# TaaraWeMosBase3.net
KiCad netlist of a schematic drawn in EAGLE
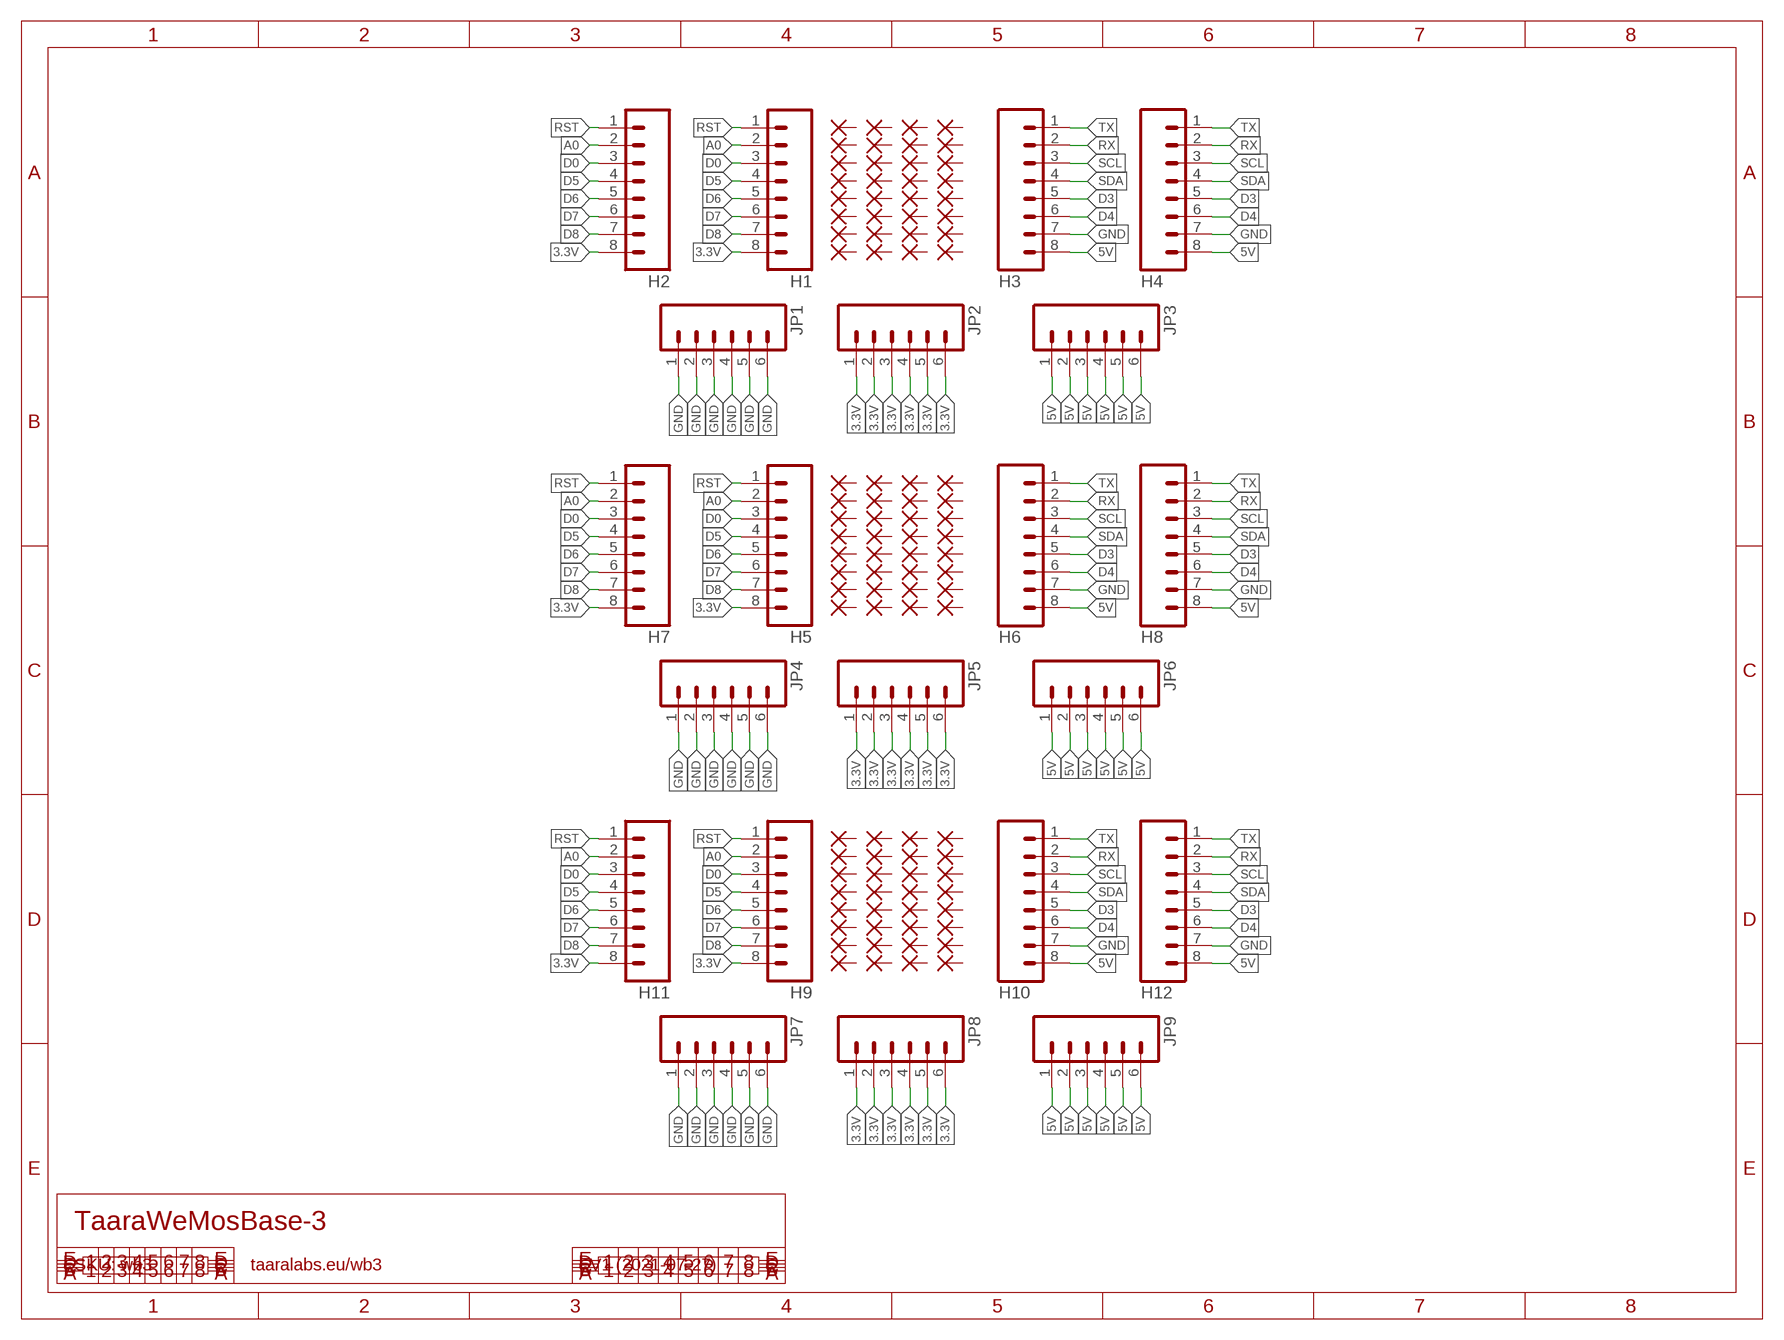
[diagram p0: schematic, sheet 1]

(export (version "E")
  (design (tool "Eeschema 10.0.6"))
  (components
    (comp (ref "H1")
      (value "M08")
      (footprint "eagle-import:1X08")
      (libsource (lib "eagle-import") (part "M08"))
    )
    (comp (ref "H2")
      (value "M08")
      (footprint "eagle-import:1X08")
      (libsource (lib "eagle-import") (part "M08"))
    )
    (comp (ref "H3")
      (value "M08")
      (footprint "eagle-import:1X08")
      (libsource (lib "eagle-import") (part "M08"))
    )
    (comp (ref "H4")
      (value "M08")
      (footprint "eagle-import:1X08")
      (libsource (lib "eagle-import") (part "M08"))
    )
    (comp (ref "H5")
      (value "M08")
      (footprint "eagle-import:1X08")
      (libsource (lib "eagle-import") (part "M08"))
    )
    (comp (ref "H6")
      (value "M08")
      (footprint "eagle-import:1X08")
      (libsource (lib "eagle-import") (part "M08"))
    )
    (comp (ref "H7")
      (value "M08")
      (footprint "eagle-import:1X08")
      (libsource (lib "eagle-import") (part "M08"))
    )
    (comp (ref "H8")
      (value "M08")
      (footprint "eagle-import:1X08")
      (libsource (lib "eagle-import") (part "M08"))
    )
    (comp (ref "H9")
      (value "M08")
      (footprint "eagle-import:1X08")
      (libsource (lib "eagle-import") (part "M08"))
    )
    (comp (ref "H10")
      (value "M08")
      (footprint "eagle-import:1X08")
      (libsource (lib "eagle-import") (part "M08"))
    )
    (comp (ref "H11")
      (value "M08")
      (footprint "eagle-import:1X08")
      (libsource (lib "eagle-import") (part "M08"))
    )
    (comp (ref "H12")
      (value "M08")
      (footprint "eagle-import:1X08")
      (libsource (lib "eagle-import") (part "M08"))
    )
    (comp (ref "JP1")
      (value "M06SIP")
      (footprint "eagle-import:1X06")
      (libsource (lib "eagle-import") (part "M06SIP"))
    )
    (comp (ref "JP2")
      (value "M06SIP")
      (footprint "eagle-import:1X06")
      (libsource (lib "eagle-import") (part "M06SIP"))
    )
    (comp (ref "JP3")
      (value "M06SIP")
      (footprint "eagle-import:1X06")
      (libsource (lib "eagle-import") (part "M06SIP"))
    )
    (comp (ref "JP4")
      (value "M06SIP")
      (footprint "eagle-import:1X06")
      (libsource (lib "eagle-import") (part "M06SIP"))
    )
    (comp (ref "JP5")
      (value "M06SIP")
      (footprint "eagle-import:1X06")
      (libsource (lib "eagle-import") (part "M06SIP"))
    )
    (comp (ref "JP6")
      (value "M06SIP")
      (footprint "eagle-import:1X06")
      (libsource (lib "eagle-import") (part "M06SIP"))
    )
    (comp (ref "JP7")
      (value "M06SIP")
      (footprint "eagle-import:1X06")
      (libsource (lib "eagle-import") (part "M06SIP"))
    )
    (comp (ref "JP8")
      (value "M06SIP")
      (footprint "eagle-import:1X06")
      (libsource (lib "eagle-import") (part "M06SIP"))
    )
    (comp (ref "JP9")
      (value "M06SIP")
      (footprint "eagle-import:1X06")
      (libsource (lib "eagle-import") (part "M06SIP"))
    )
    (comp (ref "PAD1")
      (value "1,6/0,8")
      (footprint "eagle-import:1,6_0,8")
      (libsource (lib "eagle-import") (part "1,6/0,8"))
    )
    (comp (ref "PAD2")
      (value "1,6/0,8")
      (footprint "eagle-import:1,6_0,8")
      (libsource (lib "eagle-import") (part "1,6/0,8"))
    )
    (comp (ref "PAD3")
      (value "1,6/0,8")
      (footprint "eagle-import:1,6_0,8")
      (libsource (lib "eagle-import") (part "1,6/0,8"))
    )
    (comp (ref "PAD4")
      (value "1,6/0,8")
      (footprint "eagle-import:1,6_0,8")
      (libsource (lib "eagle-import") (part "1,6/0,8"))
    )
    (comp (ref "PAD5")
      (value "1,6/0,8")
      (footprint "eagle-import:1,6_0,8")
      (libsource (lib "eagle-import") (part "1,6/0,8"))
    )
    (comp (ref "PAD6")
      (value "1,6/0,8")
      (footprint "eagle-import:1,6_0,8")
      (libsource (lib "eagle-import") (part "1,6/0,8"))
    )
    (comp (ref "PAD7")
      (value "1,6/0,8")
      (footprint "eagle-import:1,6_0,8")
      (libsource (lib "eagle-import") (part "1,6/0,8"))
    )
    (comp (ref "PAD8")
      (value "1,6/0,8")
      (footprint "eagle-import:1,6_0,8")
      (libsource (lib "eagle-import") (part "1,6/0,8"))
    )
    (comp (ref "PAD9")
      (value "1,6/0,8")
      (footprint "eagle-import:1,6_0,8")
      (libsource (lib "eagle-import") (part "1,6/0,8"))
    )
    (comp (ref "PAD10")
      (value "1,6/0,8")
      (footprint "eagle-import:1,6_0,8")
      (libsource (lib "eagle-import") (part "1,6/0,8"))
    )
    (comp (ref "PAD11")
      (value "1,6/0,8")
      (footprint "eagle-import:1,6_0,8")
      (libsource (lib "eagle-import") (part "1,6/0,8"))
    )
    (comp (ref "PAD12")
      (value "1,6/0,8")
      (footprint "eagle-import:1,6_0,8")
      (libsource (lib "eagle-import") (part "1,6/0,8"))
    )
    (comp (ref "PAD13")
      (value "1,6/0,8")
      (footprint "eagle-import:1,6_0,8")
      (libsource (lib "eagle-import") (part "1,6/0,8"))
    )
    (comp (ref "PAD14")
      (value "1,6/0,8")
      (footprint "eagle-import:1,6_0,8")
      (libsource (lib "eagle-import") (part "1,6/0,8"))
    )
    (comp (ref "PAD15")
      (value "1,6/0,8")
      (footprint "eagle-import:1,6_0,8")
      (libsource (lib "eagle-import") (part "1,6/0,8"))
    )
    (comp (ref "PAD16")
      (value "1,6/0,8")
      (footprint "eagle-import:1,6_0,8")
      (libsource (lib "eagle-import") (part "1,6/0,8"))
    )
    (comp (ref "PAD17")
      (value "1,6/0,8")
      (footprint "eagle-import:1,6_0,8")
      (libsource (lib "eagle-import") (part "1,6/0,8"))
    )
    (comp (ref "PAD18")
      (value "1,6/0,8")
      (footprint "eagle-import:1,6_0,8")
      (libsource (lib "eagle-import") (part "1,6/0,8"))
    )
    (comp (ref "PAD19")
      (value "1,6/0,8")
      (footprint "eagle-import:1,6_0,8")
      (libsource (lib "eagle-import") (part "1,6/0,8"))
    )
    (comp (ref "PAD20")
      (value "1,6/0,8")
      (footprint "eagle-import:1,6_0,8")
      (libsource (lib "eagle-import") (part "1,6/0,8"))
    )
    (comp (ref "PAD21")
      (value "1,6/0,8")
      (footprint "eagle-import:1,6_0,8")
      (libsource (lib "eagle-import") (part "1,6/0,8"))
    )
    (comp (ref "PAD22")
      (value "1,6/0,8")
      (footprint "eagle-import:1,6_0,8")
      (libsource (lib "eagle-import") (part "1,6/0,8"))
    )
    (comp (ref "PAD23")
      (value "1,6/0,8")
      (footprint "eagle-import:1,6_0,8")
      (libsource (lib "eagle-import") (part "1,6/0,8"))
    )
    (comp (ref "PAD24")
      (value "1,6/0,8")
      (footprint "eagle-import:1,6_0,8")
      (libsource (lib "eagle-import") (part "1,6/0,8"))
    )
    (comp (ref "PAD25")
      (value "1,6/0,8")
      (footprint "eagle-import:1,6_0,8")
      (libsource (lib "eagle-import") (part "1,6/0,8"))
    )
    (comp (ref "PAD26")
      (value "1,6/0,8")
      (footprint "eagle-import:1,6_0,8")
      (libsource (lib "eagle-import") (part "1,6/0,8"))
    )
    (comp (ref "PAD27")
      (value "1,6/0,8")
      (footprint "eagle-import:1,6_0,8")
      (libsource (lib "eagle-import") (part "1,6/0,8"))
    )
    (comp (ref "PAD28")
      (value "1,6/0,8")
      (footprint "eagle-import:1,6_0,8")
      (libsource (lib "eagle-import") (part "1,6/0,8"))
    )
    (comp (ref "PAD29")
      (value "1,6/0,8")
      (footprint "eagle-import:1,6_0,8")
      (libsource (lib "eagle-import") (part "1,6/0,8"))
    )
    (comp (ref "PAD30")
      (value "1,6/0,8")
      (footprint "eagle-import:1,6_0,8")
      (libsource (lib "eagle-import") (part "1,6/0,8"))
    )
    (comp (ref "PAD31")
      (value "1,6/0,8")
      (footprint "eagle-import:1,6_0,8")
      (libsource (lib "eagle-import") (part "1,6/0,8"))
    )
    (comp (ref "PAD32")
      (value "1,6/0,8")
      (footprint "eagle-import:1,6_0,8")
      (libsource (lib "eagle-import") (part "1,6/0,8"))
    )
    (comp (ref "PAD33")
      (value "1,6/0,8")
      (footprint "eagle-import:1,6_0,8")
      (libsource (lib "eagle-import") (part "1,6/0,8"))
    )
    (comp (ref "PAD34")
      (value "1,6/0,8")
      (footprint "eagle-import:1,6_0,8")
      (libsource (lib "eagle-import") (part "1,6/0,8"))
    )
    (comp (ref "PAD35")
      (value "1,6/0,8")
      (footprint "eagle-import:1,6_0,8")
      (libsource (lib "eagle-import") (part "1,6/0,8"))
    )
    (comp (ref "PAD36")
      (value "1,6/0,8")
      (footprint "eagle-import:1,6_0,8")
      (libsource (lib "eagle-import") (part "1,6/0,8"))
    )
    (comp (ref "PAD37")
      (value "1,6/0,8")
      (footprint "eagle-import:1,6_0,8")
      (libsource (lib "eagle-import") (part "1,6/0,8"))
    )
    (comp (ref "PAD38")
      (value "1,6/0,8")
      (footprint "eagle-import:1,6_0,8")
      (libsource (lib "eagle-import") (part "1,6/0,8"))
    )
    (comp (ref "PAD39")
      (value "1,6/0,8")
      (footprint "eagle-import:1,6_0,8")
      (libsource (lib "eagle-import") (part "1,6/0,8"))
    )
    (comp (ref "PAD40")
      (value "1,6/0,8")
      (footprint "eagle-import:1,6_0,8")
      (libsource (lib "eagle-import") (part "1,6/0,8"))
    )
    (comp (ref "PAD41")
      (value "1,6/0,8")
      (footprint "eagle-import:1,6_0,8")
      (libsource (lib "eagle-import") (part "1,6/0,8"))
    )
    (comp (ref "PAD42")
      (value "1,6/0,8")
      (footprint "eagle-import:1,6_0,8")
      (libsource (lib "eagle-import") (part "1,6/0,8"))
    )
    (comp (ref "PAD43")
      (value "1,6/0,8")
      (footprint "eagle-import:1,6_0,8")
      (libsource (lib "eagle-import") (part "1,6/0,8"))
    )
    (comp (ref "PAD44")
      (value "1,6/0,8")
      (footprint "eagle-import:1,6_0,8")
      (libsource (lib "eagle-import") (part "1,6/0,8"))
    )
    (comp (ref "PAD45")
      (value "1,6/0,8")
      (footprint "eagle-import:1,6_0,8")
      (libsource (lib "eagle-import") (part "1,6/0,8"))
    )
    (comp (ref "PAD46")
      (value "1,6/0,8")
      (footprint "eagle-import:1,6_0,8")
      (libsource (lib "eagle-import") (part "1,6/0,8"))
    )
    (comp (ref "PAD47")
      (value "1,6/0,8")
      (footprint "eagle-import:1,6_0,8")
      (libsource (lib "eagle-import") (part "1,6/0,8"))
    )
    (comp (ref "PAD48")
      (value "1,6/0,8")
      (footprint "eagle-import:1,6_0,8")
      (libsource (lib "eagle-import") (part "1,6/0,8"))
    )
    (comp (ref "PAD49")
      (value "1,6/0,8")
      (footprint "eagle-import:1,6_0,8")
      (libsource (lib "eagle-import") (part "1,6/0,8"))
    )
    (comp (ref "PAD50")
      (value "1,6/0,8")
      (footprint "eagle-import:1,6_0,8")
      (libsource (lib "eagle-import") (part "1,6/0,8"))
    )
    (comp (ref "PAD51")
      (value "1,6/0,8")
      (footprint "eagle-import:1,6_0,8")
      (libsource (lib "eagle-import") (part "1,6/0,8"))
    )
    (comp (ref "PAD52")
      (value "1,6/0,8")
      (footprint "eagle-import:1,6_0,8")
      (libsource (lib "eagle-import") (part "1,6/0,8"))
    )
    (comp (ref "PAD53")
      (value "1,6/0,8")
      (footprint "eagle-import:1,6_0,8")
      (libsource (lib "eagle-import") (part "1,6/0,8"))
    )
    (comp (ref "PAD54")
      (value "1,6/0,8")
      (footprint "eagle-import:1,6_0,8")
      (libsource (lib "eagle-import") (part "1,6/0,8"))
    )
    (comp (ref "PAD55")
      (value "1,6/0,8")
      (footprint "eagle-import:1,6_0,8")
      (libsource (lib "eagle-import") (part "1,6/0,8"))
    )
    (comp (ref "PAD56")
      (value "1,6/0,8")
      (footprint "eagle-import:1,6_0,8")
      (libsource (lib "eagle-import") (part "1,6/0,8"))
    )
    (comp (ref "PAD57")
      (value "1,6/0,8")
      (footprint "eagle-import:1,6_0,8")
      (libsource (lib "eagle-import") (part "1,6/0,8"))
    )
    (comp (ref "PAD58")
      (value "1,6/0,8")
      (footprint "eagle-import:1,6_0,8")
      (libsource (lib "eagle-import") (part "1,6/0,8"))
    )
    (comp (ref "PAD59")
      (value "1,6/0,8")
      (footprint "eagle-import:1,6_0,8")
      (libsource (lib "eagle-import") (part "1,6/0,8"))
    )
    (comp (ref "PAD60")
      (value "1,6/0,8")
      (footprint "eagle-import:1,6_0,8")
      (libsource (lib "eagle-import") (part "1,6/0,8"))
    )
    (comp (ref "PAD61")
      (value "1,6/0,8")
      (footprint "eagle-import:1,6_0,8")
      (libsource (lib "eagle-import") (part "1,6/0,8"))
    )
    (comp (ref "PAD62")
      (value "1,6/0,8")
      (footprint "eagle-import:1,6_0,8")
      (libsource (lib "eagle-import") (part "1,6/0,8"))
    )
    (comp (ref "PAD63")
      (value "1,6/0,8")
      (footprint "eagle-import:1,6_0,8")
      (libsource (lib "eagle-import") (part "1,6/0,8"))
    )
    (comp (ref "PAD64")
      (value "1,6/0,8")
      (footprint "eagle-import:1,6_0,8")
      (libsource (lib "eagle-import") (part "1,6/0,8"))
    )
    (comp (ref "PAD65")
      (value "1,6/0,8")
      (footprint "eagle-import:1,6_0,8")
      (libsource (lib "eagle-import") (part "1,6/0,8"))
    )
    (comp (ref "PAD66")
      (value "1,6/0,8")
      (footprint "eagle-import:1,6_0,8")
      (libsource (lib "eagle-import") (part "1,6/0,8"))
    )
    (comp (ref "PAD67")
      (value "1,6/0,8")
      (footprint "eagle-import:1,6_0,8")
      (libsource (lib "eagle-import") (part "1,6/0,8"))
    )
    (comp (ref "PAD68")
      (value "1,6/0,8")
      (footprint "eagle-import:1,6_0,8")
      (libsource (lib "eagle-import") (part "1,6/0,8"))
    )
    (comp (ref "PAD69")
      (value "1,6/0,8")
      (footprint "eagle-import:1,6_0,8")
      (libsource (lib "eagle-import") (part "1,6/0,8"))
    )
    (comp (ref "PAD70")
      (value "1,6/0,8")
      (footprint "eagle-import:1,6_0,8")
      (libsource (lib "eagle-import") (part "1,6/0,8"))
    )
    (comp (ref "PAD71")
      (value "1,6/0,8")
      (footprint "eagle-import:1,6_0,8")
      (libsource (lib "eagle-import") (part "1,6/0,8"))
    )
    (comp (ref "PAD72")
      (value "1,6/0,8")
      (footprint "eagle-import:1,6_0,8")
      (libsource (lib "eagle-import") (part "1,6/0,8"))
    )
    (comp (ref "PAD73")
      (value "1,6/0,8")
      (footprint "eagle-import:1,6_0,8")
      (libsource (lib "eagle-import") (part "1,6/0,8"))
    )
    (comp (ref "PAD74")
      (value "1,6/0,8")
      (footprint "eagle-import:1,6_0,8")
      (libsource (lib "eagle-import") (part "1,6/0,8"))
    )
    (comp (ref "PAD75")
      (value "1,6/0,8")
      (footprint "eagle-import:1,6_0,8")
      (libsource (lib "eagle-import") (part "1,6/0,8"))
    )
    (comp (ref "PAD76")
      (value "1,6/0,8")
      (footprint "eagle-import:1,6_0,8")
      (libsource (lib "eagle-import") (part "1,6/0,8"))
    )
    (comp (ref "PAD77")
      (value "1,6/0,8")
      (footprint "eagle-import:1,6_0,8")
      (libsource (lib "eagle-import") (part "1,6/0,8"))
    )
    (comp (ref "PAD78")
      (value "1,6/0,8")
      (footprint "eagle-import:1,6_0,8")
      (libsource (lib "eagle-import") (part "1,6/0,8"))
    )
    (comp (ref "PAD79")
      (value "1,6/0,8")
      (footprint "eagle-import:1,6_0,8")
      (libsource (lib "eagle-import") (part "1,6/0,8"))
    )
    (comp (ref "PAD80")
      (value "1,6/0,8")
      (footprint "eagle-import:1,6_0,8")
      (libsource (lib "eagle-import") (part "1,6/0,8"))
    )
    (comp (ref "PAD81")
      (value "1,6/0,8")
      (footprint "eagle-import:1,6_0,8")
      (libsource (lib "eagle-import") (part "1,6/0,8"))
    )
    (comp (ref "PAD82")
      (value "1,6/0,8")
      (footprint "eagle-import:1,6_0,8")
      (libsource (lib "eagle-import") (part "1,6/0,8"))
    )
    (comp (ref "PAD83")
      (value "1,6/0,8")
      (footprint "eagle-import:1,6_0,8")
      (libsource (lib "eagle-import") (part "1,6/0,8"))
    )
    (comp (ref "PAD84")
      (value "1,6/0,8")
      (footprint "eagle-import:1,6_0,8")
      (libsource (lib "eagle-import") (part "1,6/0,8"))
    )
    (comp (ref "PAD85")
      (value "1,6/0,8")
      (footprint "eagle-import:1,6_0,8")
      (libsource (lib "eagle-import") (part "1,6/0,8"))
    )
    (comp (ref "PAD86")
      (value "1,6/0,8")
      (footprint "eagle-import:1,6_0,8")
      (libsource (lib "eagle-import") (part "1,6/0,8"))
    )
    (comp (ref "PAD87")
      (value "1,6/0,8")
      (footprint "eagle-import:1,6_0,8")
      (libsource (lib "eagle-import") (part "1,6/0,8"))
    )
    (comp (ref "PAD88")
      (value "1,6/0,8")
      (footprint "eagle-import:1,6_0,8")
      (libsource (lib "eagle-import") (part "1,6/0,8"))
    )
    (comp (ref "PAD89")
      (value "1,6/0,8")
      (footprint "eagle-import:1,6_0,8")
      (libsource (lib "eagle-import") (part "1,6/0,8"))
    )
    (comp (ref "PAD90")
      (value "1,6/0,8")
      (footprint "eagle-import:1,6_0,8")
      (libsource (lib "eagle-import") (part "1,6/0,8"))
    )
    (comp (ref "PAD91")
      (value "1,6/0,8")
      (footprint "eagle-import:1,6_0,8")
      (libsource (lib "eagle-import") (part "1,6/0,8"))
    )
    (comp (ref "PAD92")
      (value "1,6/0,8")
      (footprint "eagle-import:1,6_0,8")
      (libsource (lib "eagle-import") (part "1,6/0,8"))
    )
    (comp (ref "PAD93")
      (value "1,6/0,8")
      (footprint "eagle-import:1,6_0,8")
      (libsource (lib "eagle-import") (part "1,6/0,8"))
    )
    (comp (ref "PAD94")
      (value "1,6/0,8")
      (footprint "eagle-import:1,6_0,8")
      (libsource (lib "eagle-import") (part "1,6/0,8"))
    )
    (comp (ref "PAD95")
      (value "1,6/0,8")
      (footprint "eagle-import:1,6_0,8")
      (libsource (lib "eagle-import") (part "1,6/0,8"))
    )
    (comp (ref "PAD96")
      (value "1,6/0,8")
      (footprint "eagle-import:1,6_0,8")
      (libsource (lib "eagle-import") (part "1,6/0,8"))
    )
  )
  (nets
    (net (code "1") (name "3.3V") (class "Default")
      (node (ref "H1") (pin "8") (pinfunction "8_8") (pintype "passive"))
      (node (ref "H11") (pin "8") (pinfunction "8_8") (pintype "passive"))
      (node (ref "H2") (pin "8") (pinfunction "8_8") (pintype "passive"))
      (node (ref "H5") (pin "8") (pinfunction "8_8") (pintype "passive"))
      (node (ref "H7") (pin "8") (pinfunction "8_8") (pintype "passive"))
      (node (ref "H9") (pin "8") (pinfunction "8_8") (pintype "passive"))
      (node (ref "JP2") (pin "1") (pinfunction "1_1") (pintype "passive"))
      (node (ref "JP2") (pin "2") (pinfunction "2_2") (pintype "passive"))
      (node (ref "JP2") (pin "3") (pinfunction "3_3") (pintype "passive"))
      (node (ref "JP2") (pin "4") (pinfunction "4_4") (pintype "passive"))
      (node (ref "JP2") (pin "5") (pinfunction "5_5") (pintype "passive"))
      (node (ref "JP2") (pin "6") (pinfunction "6_6") (pintype "passive"))
      (node (ref "JP5") (pin "1") (pinfunction "1_1") (pintype "passive"))
      (node (ref "JP5") (pin "2") (pinfunction "2_2") (pintype "passive"))
      (node (ref "JP5") (pin "3") (pinfunction "3_3") (pintype "passive"))
      (node (ref "JP5") (pin "4") (pinfunction "4_4") (pintype "passive"))
      (node (ref "JP5") (pin "5") (pinfunction "5_5") (pintype "passive"))
      (node (ref "JP5") (pin "6") (pinfunction "6_6") (pintype "passive"))
      (node (ref "JP8") (pin "1") (pinfunction "1_1") (pintype "passive"))
      (node (ref "JP8") (pin "2") (pinfunction "2_2") (pintype "passive"))
      (node (ref "JP8") (pin "3") (pinfunction "3_3") (pintype "passive"))
      (node (ref "JP8") (pin "4") (pinfunction "4_4") (pintype "passive"))
      (node (ref "JP8") (pin "5") (pinfunction "5_5") (pintype "passive"))
      (node (ref "JP8") (pin "6") (pinfunction "6_6") (pintype "passive"))
    )
    (net (code "2") (name "5V") (class "Default")
      (node (ref "H10") (pin "8") (pinfunction "8_8") (pintype "passive"))
      (node (ref "H12") (pin "8") (pinfunction "8_8") (pintype "passive"))
      (node (ref "H3") (pin "8") (pinfunction "8_8") (pintype "passive"))
      (node (ref "H4") (pin "8") (pinfunction "8_8") (pintype "passive"))
      (node (ref "H6") (pin "8") (pinfunction "8_8") (pintype "passive"))
      (node (ref "H8") (pin "8") (pinfunction "8_8") (pintype "passive"))
      (node (ref "JP3") (pin "1") (pinfunction "1_1") (pintype "passive"))
      (node (ref "JP3") (pin "2") (pinfunction "2_2") (pintype "passive"))
      (node (ref "JP3") (pin "3") (pinfunction "3_3") (pintype "passive"))
      (node (ref "JP3") (pin "4") (pinfunction "4_4") (pintype "passive"))
      (node (ref "JP3") (pin "5") (pinfunction "5_5") (pintype "passive"))
      (node (ref "JP3") (pin "6") (pinfunction "6_6") (pintype "passive"))
      (node (ref "JP6") (pin "1") (pinfunction "1_1") (pintype "passive"))
      (node (ref "JP6") (pin "2") (pinfunction "2_2") (pintype "passive"))
      (node (ref "JP6") (pin "3") (pinfunction "3_3") (pintype "passive"))
      (node (ref "JP6") (pin "4") (pinfunction "4_4") (pintype "passive"))
      (node (ref "JP6") (pin "5") (pinfunction "5_5") (pintype "passive"))
      (node (ref "JP6") (pin "6") (pinfunction "6_6") (pintype "passive"))
      (node (ref "JP9") (pin "1") (pinfunction "1_1") (pintype "passive"))
      (node (ref "JP9") (pin "2") (pinfunction "2_2") (pintype "passive"))
      (node (ref "JP9") (pin "3") (pinfunction "3_3") (pintype "passive"))
      (node (ref "JP9") (pin "4") (pinfunction "4_4") (pintype "passive"))
      (node (ref "JP9") (pin "5") (pinfunction "5_5") (pintype "passive"))
      (node (ref "JP9") (pin "6") (pinfunction "6_6") (pintype "passive"))
    )
    (net (code "3") (name "A0") (class "Default")
      (node (ref "H1") (pin "2") (pinfunction "2_2") (pintype "passive"))
      (node (ref "H11") (pin "2") (pinfunction "2_2") (pintype "passive"))
      (node (ref "H2") (pin "2") (pinfunction "2_2") (pintype "passive"))
      (node (ref "H5") (pin "2") (pinfunction "2_2") (pintype "passive"))
      (node (ref "H7") (pin "2") (pinfunction "2_2") (pintype "passive"))
      (node (ref "H9") (pin "2") (pinfunction "2_2") (pintype "passive"))
    )
    (net (code "4") (name "D0") (class "Default")
      (node (ref "H1") (pin "3") (pinfunction "3_3") (pintype "passive"))
      (node (ref "H11") (pin "3") (pinfunction "3_3") (pintype "passive"))
      (node (ref "H2") (pin "3") (pinfunction "3_3") (pintype "passive"))
      (node (ref "H5") (pin "3") (pinfunction "3_3") (pintype "passive"))
      (node (ref "H7") (pin "3") (pinfunction "3_3") (pintype "passive"))
      (node (ref "H9") (pin "3") (pinfunction "3_3") (pintype "passive"))
    )
    (net (code "5") (name "D3") (class "Default")
      (node (ref "H10") (pin "5") (pinfunction "5_5") (pintype "passive"))
      (node (ref "H12") (pin "5") (pinfunction "5_5") (pintype "passive"))
      (node (ref "H3") (pin "5") (pinfunction "5_5") (pintype "passive"))
      (node (ref "H4") (pin "5") (pinfunction "5_5") (pintype "passive"))
      (node (ref "H6") (pin "5") (pinfunction "5_5") (pintype "passive"))
      (node (ref "H8") (pin "5") (pinfunction "5_5") (pintype "passive"))
    )
    (net (code "6") (name "D4") (class "Default")
      (node (ref "H10") (pin "6") (pinfunction "6_6") (pintype "passive"))
      (node (ref "H12") (pin "6") (pinfunction "6_6") (pintype "passive"))
      (node (ref "H3") (pin "6") (pinfunction "6_6") (pintype "passive"))
      (node (ref "H4") (pin "6") (pinfunction "6_6") (pintype "passive"))
      (node (ref "H6") (pin "6") (pinfunction "6_6") (pintype "passive"))
      (node (ref "H8") (pin "6") (pinfunction "6_6") (pintype "passive"))
    )
    (net (code "7") (name "D5") (class "Default")
      (node (ref "H1") (pin "4") (pinfunction "4_4") (pintype "passive"))
      (node (ref "H11") (pin "4") (pinfunction "4_4") (pintype "passive"))
      (node (ref "H2") (pin "4") (pinfunction "4_4") (pintype "passive"))
      (node (ref "H5") (pin "4") (pinfunction "4_4") (pintype "passive"))
      (node (ref "H7") (pin "4") (pinfunction "4_4") (pintype "passive"))
      (node (ref "H9") (pin "4") (pinfunction "4_4") (pintype "passive"))
    )
    (net (code "8") (name "D6") (class "Default")
      (node (ref "H1") (pin "5") (pinfunction "5_5") (pintype "passive"))
      (node (ref "H11") (pin "5") (pinfunction "5_5") (pintype "passive"))
      (node (ref "H2") (pin "5") (pinfunction "5_5") (pintype "passive"))
      (node (ref "H5") (pin "5") (pinfunction "5_5") (pintype "passive"))
      (node (ref "H7") (pin "5") (pinfunction "5_5") (pintype "passive"))
      (node (ref "H9") (pin "5") (pinfunction "5_5") (pintype "passive"))
    )
    (net (code "9") (name "D7") (class "Default")
      (node (ref "H1") (pin "6") (pinfunction "6_6") (pintype "passive"))
      (node (ref "H11") (pin "6") (pinfunction "6_6") (pintype "passive"))
      (node (ref "H2") (pin "6") (pinfunction "6_6") (pintype "passive"))
      (node (ref "H5") (pin "6") (pinfunction "6_6") (pintype "passive"))
      (node (ref "H7") (pin "6") (pinfunction "6_6") (pintype "passive"))
      (node (ref "H9") (pin "6") (pinfunction "6_6") (pintype "passive"))
    )
    (net (code "10") (name "D8") (class "Default")
      (node (ref "H1") (pin "7") (pinfunction "7_7") (pintype "passive"))
      (node (ref "H11") (pin "7") (pinfunction "7_7") (pintype "passive"))
      (node (ref "H2") (pin "7") (pinfunction "7_7") (pintype "passive"))
      (node (ref "H5") (pin "7") (pinfunction "7_7") (pintype "passive"))
      (node (ref "H7") (pin "7") (pinfunction "7_7") (pintype "passive"))
      (node (ref "H9") (pin "7") (pinfunction "7_7") (pintype "passive"))
    )
    (net (code "11") (name "GND") (class "Default")
      (node (ref "H10") (pin "7") (pinfunction "7_7") (pintype "passive"))
      (node (ref "H12") (pin "7") (pinfunction "7_7") (pintype "passive"))
      (node (ref "H3") (pin "7") (pinfunction "7_7") (pintype "passive"))
      (node (ref "H4") (pin "7") (pinfunction "7_7") (pintype "passive"))
      (node (ref "H6") (pin "7") (pinfunction "7_7") (pintype "passive"))
      (node (ref "H8") (pin "7") (pinfunction "7_7") (pintype "passive"))
      (node (ref "JP1") (pin "1") (pinfunction "1_1") (pintype "passive"))
      (node (ref "JP1") (pin "2") (pinfunction "2_2") (pintype "passive"))
      (node (ref "JP1") (pin "3") (pinfunction "3_3") (pintype "passive"))
      (node (ref "JP1") (pin "4") (pinfunction "4_4") (pintype "passive"))
      (node (ref "JP1") (pin "5") (pinfunction "5_5") (pintype "passive"))
      (node (ref "JP1") (pin "6") (pinfunction "6_6") (pintype "passive"))
      (node (ref "JP4") (pin "1") (pinfunction "1_1") (pintype "passive"))
      (node (ref "JP4") (pin "2") (pinfunction "2_2") (pintype "passive"))
      (node (ref "JP4") (pin "3") (pinfunction "3_3") (pintype "passive"))
      (node (ref "JP4") (pin "4") (pinfunction "4_4") (pintype "passive"))
      (node (ref "JP4") (pin "5") (pinfunction "5_5") (pintype "passive"))
      (node (ref "JP4") (pin "6") (pinfunction "6_6") (pintype "passive"))
      (node (ref "JP7") (pin "1") (pinfunction "1_1") (pintype "passive"))
      (node (ref "JP7") (pin "2") (pinfunction "2_2") (pintype "passive"))
      (node (ref "JP7") (pin "3") (pinfunction "3_3") (pintype "passive"))
      (node (ref "JP7") (pin "4") (pinfunction "4_4") (pintype "passive"))
      (node (ref "JP7") (pin "5") (pinfunction "5_5") (pintype "passive"))
      (node (ref "JP7") (pin "6") (pinfunction "6_6") (pintype "passive"))
    )
    (net (code "12") (name "RST") (class "Default")
      (node (ref "H1") (pin "1") (pinfunction "1_1") (pintype "passive"))
      (node (ref "H11") (pin "1") (pinfunction "1_1") (pintype "passive"))
      (node (ref "H2") (pin "1") (pinfunction "1_1") (pintype "passive"))
      (node (ref "H5") (pin "1") (pinfunction "1_1") (pintype "passive"))
      (node (ref "H7") (pin "1") (pinfunction "1_1") (pintype "passive"))
      (node (ref "H9") (pin "1") (pinfunction "1_1") (pintype "passive"))
    )
    (net (code "13") (name "RX") (class "Default")
      (node (ref "H10") (pin "2") (pinfunction "2_2") (pintype "passive"))
      (node (ref "H12") (pin "2") (pinfunction "2_2") (pintype "passive"))
      (node (ref "H3") (pin "2") (pinfunction "2_2") (pintype "passive"))
      (node (ref "H4") (pin "2") (pinfunction "2_2") (pintype "passive"))
      (node (ref "H6") (pin "2") (pinfunction "2_2") (pintype "passive"))
      (node (ref "H8") (pin "2") (pinfunction "2_2") (pintype "passive"))
    )
    (net (code "14") (name "SCL") (class "Default")
      (node (ref "H10") (pin "3") (pinfunction "3_3") (pintype "passive"))
      (node (ref "H12") (pin "3") (pinfunction "3_3") (pintype "passive"))
      (node (ref "H3") (pin "3") (pinfunction "3_3") (pintype "passive"))
      (node (ref "H4") (pin "3") (pinfunction "3_3") (pintype "passive"))
      (node (ref "H6") (pin "3") (pinfunction "3_3") (pintype "passive"))
      (node (ref "H8") (pin "3") (pinfunction "3_3") (pintype "passive"))
    )
    (net (code "15") (name "SDA") (class "Default")
      (node (ref "H10") (pin "4") (pinfunction "4_4") (pintype "passive"))
      (node (ref "H12") (pin "4") (pinfunction "4_4") (pintype "passive"))
      (node (ref "H3") (pin "4") (pinfunction "4_4") (pintype "passive"))
      (node (ref "H4") (pin "4") (pinfunction "4_4") (pintype "passive"))
      (node (ref "H6") (pin "4") (pinfunction "4_4") (pintype "passive"))
      (node (ref "H8") (pin "4") (pinfunction "4_4") (pintype "passive"))
    )
    (net (code "16") (name "TX") (class "Default")
      (node (ref "H10") (pin "1") (pinfunction "1_1") (pintype "passive"))
      (node (ref "H12") (pin "1") (pinfunction "1_1") (pintype "passive"))
      (node (ref "H3") (pin "1") (pinfunction "1_1") (pintype "passive"))
      (node (ref "H4") (pin "1") (pinfunction "1_1") (pintype "passive"))
      (node (ref "H6") (pin "1") (pinfunction "1_1") (pintype "passive"))
      (node (ref "H8") (pin "1") (pinfunction "1_1") (pintype "passive"))
    )
    (net (code "17") (name "unconnected-(PAD1-P-Pad1)") (class "Default")
      (node (ref "PAD1") (pin "1") (pinfunction "P_1") (pintype "passive"))
    )
    (net (code "18") (name "unconnected-(PAD2-P-Pad1)") (class "Default")
      (node (ref "PAD2") (pin "1") (pinfunction "P_1") (pintype "passive"))
    )
    (net (code "19") (name "unconnected-(PAD3-P-Pad1)") (class "Default")
      (node (ref "PAD3") (pin "1") (pinfunction "P_1") (pintype "passive"))
    )
    (net (code "20") (name "unconnected-(PAD4-P-Pad1)") (class "Default")
      (node (ref "PAD4") (pin "1") (pinfunction "P_1") (pintype "passive"))
    )
    (net (code "21") (name "unconnected-(PAD5-P-Pad1)") (class "Default")
      (node (ref "PAD5") (pin "1") (pinfunction "P_1") (pintype "passive"))
    )
    (net (code "22") (name "unconnected-(PAD6-P-Pad1)") (class "Default")
      (node (ref "PAD6") (pin "1") (pinfunction "P_1") (pintype "passive"))
    )
    (net (code "23") (name "unconnected-(PAD7-P-Pad1)") (class "Default")
      (node (ref "PAD7") (pin "1") (pinfunction "P_1") (pintype "passive"))
    )
    (net (code "24") (name "unconnected-(PAD8-P-Pad1)") (class "Default")
      (node (ref "PAD8") (pin "1") (pinfunction "P_1") (pintype "passive"))
    )
    (net (code "25") (name "unconnected-(PAD9-P-Pad1)") (class "Default")
      (node (ref "PAD9") (pin "1") (pinfunction "P_1") (pintype "passive"))
    )
    (net (code "26") (name "unconnected-(PAD10-P-Pad1)") (class "Default")
      (node (ref "PAD10") (pin "1") (pinfunction "P_1") (pintype "passive"))
    )
    (net (code "27") (name "unconnected-(PAD11-P-Pad1)") (class "Default")
      (node (ref "PAD11") (pin "1") (pinfunction "P_1") (pintype "passive"))
    )
    (net (code "28") (name "unconnected-(PAD12-P-Pad1)") (class "Default")
      (node (ref "PAD12") (pin "1") (pinfunction "P_1") (pintype "passive"))
    )
    (net (code "29") (name "unconnected-(PAD13-P-Pad1)") (class "Default")
      (node (ref "PAD13") (pin "1") (pinfunction "P_1") (pintype "passive"))
    )
    (net (code "30") (name "unconnected-(PAD14-P-Pad1)") (class "Default")
      (node (ref "PAD14") (pin "1") (pinfunction "P_1") (pintype "passive"))
    )
    (net (code "31") (name "unconnected-(PAD15-P-Pad1)") (class "Default")
      (node (ref "PAD15") (pin "1") (pinfunction "P_1") (pintype "passive"))
    )
    (net (code "32") (name "unconnected-(PAD16-P-Pad1)") (class "Default")
      (node (ref "PAD16") (pin "1") (pinfunction "P_1") (pintype "passive"))
    )
    (net (code "33") (name "unconnected-(PAD17-P-Pad1)") (class "Default")
      (node (ref "PAD17") (pin "1") (pinfunction "P_1") (pintype "passive"))
    )
    (net (code "34") (name "unconnected-(PAD18-P-Pad1)") (class "Default")
      (node (ref "PAD18") (pin "1") (pinfunction "P_1") (pintype "passive"))
    )
    (net (code "35") (name "unconnected-(PAD19-P-Pad1)") (class "Default")
      (node (ref "PAD19") (pin "1") (pinfunction "P_1") (pintype "passive"))
    )
    (net (code "36") (name "unconnected-(PAD20-P-Pad1)") (class "Default")
      (node (ref "PAD20") (pin "1") (pinfunction "P_1") (pintype "passive"))
    )
    (net (code "37") (name "unconnected-(PAD21-P-Pad1)") (class "Default")
      (node (ref "PAD21") (pin "1") (pinfunction "P_1") (pintype "passive"))
    )
    (net (code "38") (name "unconnected-(PAD22-P-Pad1)") (class "Default")
      (node (ref "PAD22") (pin "1") (pinfunction "P_1") (pintype "passive"))
    )
    (net (code "39") (name "unconnected-(PAD23-P-Pad1)") (class "Default")
      (node (ref "PAD23") (pin "1") (pinfunction "P_1") (pintype "passive"))
    )
    (net (code "40") (name "unconnected-(PAD24-P-Pad1)") (class "Default")
      (node (ref "PAD24") (pin "1") (pinfunction "P_1") (pintype "passive"))
    )
    (net (code "41") (name "unconnected-(PAD25-P-Pad1)") (class "Default")
      (node (ref "PAD25") (pin "1") (pinfunction "P_1") (pintype "passive"))
    )
    (net (code "42") (name "unconnected-(PAD26-P-Pad1)") (class "Default")
      (node (ref "PAD26") (pin "1") (pinfunction "P_1") (pintype "passive"))
    )
    (net (code "43") (name "unconnected-(PAD27-P-Pad1)") (class "Default")
      (node (ref "PAD27") (pin "1") (pinfunction "P_1") (pintype "passive"))
    )
    (net (code "44") (name "unconnected-(PAD28-P-Pad1)") (class "Default")
      (node (ref "PAD28") (pin "1") (pinfunction "P_1") (pintype "passive"))
    )
    (net (code "45") (name "unconnected-(PAD29-P-Pad1)") (class "Default")
      (node (ref "PAD29") (pin "1") (pinfunction "P_1") (pintype "passive"))
    )
    (net (code "46") (name "unconnected-(PAD30-P-Pad1)") (class "Default")
      (node (ref "PAD30") (pin "1") (pinfunction "P_1") (pintype "passive"))
    )
    (net (code "47") (name "unconnected-(PAD31-P-Pad1)") (class "Default")
      (node (ref "PAD31") (pin "1") (pinfunction "P_1") (pintype "passive"))
    )
    (net (code "48") (name "unconnected-(PAD32-P-Pad1)") (class "Default")
      (node (ref "PAD32") (pin "1") (pinfunction "P_1") (pintype "passive"))
    )
    (net (code "49") (name "unconnected-(PAD33-P-Pad1)") (class "Default")
      (node (ref "PAD33") (pin "1") (pinfunction "P_1") (pintype "passive"))
    )
    (net (code "50") (name "unconnected-(PAD34-P-Pad1)") (class "Default")
      (node (ref "PAD34") (pin "1") (pinfunction "P_1") (pintype "passive"))
    )
    (net (code "51") (name "unconnected-(PAD35-P-Pad1)") (class "Default")
      (node (ref "PAD35") (pin "1") (pinfunction "P_1") (pintype "passive"))
    )
    (net (code "52") (name "unconnected-(PAD36-P-Pad1)") (class "Default")
      (node (ref "PAD36") (pin "1") (pinfunction "P_1") (pintype "passive"))
    )
    (net (code "53") (name "unconnected-(PAD37-P-Pad1)") (class "Default")
      (node (ref "PAD37") (pin "1") (pinfunction "P_1") (pintype "passive"))
    )
    (net (code "54") (name "unconnected-(PAD38-P-Pad1)") (class "Default")
      (node (ref "PAD38") (pin "1") (pinfunction "P_1") (pintype "passive"))
    )
    (net (code "55") (name "unconnected-(PAD39-P-Pad1)") (class "Default")
      (node (ref "PAD39") (pin "1") (pinfunction "P_1") (pintype "passive"))
    )
    (net (code "56") (name "unconnected-(PAD40-P-Pad1)") (class "Default")
      (node (ref "PAD40") (pin "1") (pinfunction "P_1") (pintype "passive"))
    )
    (net (code "57") (name "unconnected-(PAD41-P-Pad1)") (class "Default")
      (node (ref "PAD41") (pin "1") (pinfunction "P_1") (pintype "passive"))
    )
    (net (code "58") (name "unconnected-(PAD42-P-Pad1)") (class "Default")
      (node (ref "PAD42") (pin "1") (pinfunction "P_1") (pintype "passive"))
    )
    (net (code "59") (name "unconnected-(PAD43-P-Pad1)") (class "Default")
      (node (ref "PAD43") (pin "1") (pinfunction "P_1") (pintype "passive"))
    )
    (net (code "60") (name "unconnected-(PAD44-P-Pad1)") (class "Default")
      (node (ref "PAD44") (pin "1") (pinfunction "P_1") (pintype "passive"))
    )
    (net (code "61") (name "unconnected-(PAD45-P-Pad1)") (class "Default")
      (node (ref "PAD45") (pin "1") (pinfunction "P_1") (pintype "passive"))
    )
    (net (code "62") (name "unconnected-(PAD46-P-Pad1)") (class "Default")
      (node (ref "PAD46") (pin "1") (pinfunction "P_1") (pintype "passive"))
    )
    (net (code "63") (name "unconnected-(PAD47-P-Pad1)") (class "Default")
      (node (ref "PAD47") (pin "1") (pinfunction "P_1") (pintype "passive"))
    )
    (net (code "64") (name "unconnected-(PAD48-P-Pad1)") (class "Default")
      (node (ref "PAD48") (pin "1") (pinfunction "P_1") (pintype "passive"))
    )
    (net (code "65") (name "unconnected-(PAD49-P-Pad1)") (class "Default")
      (node (ref "PAD49") (pin "1") (pinfunction "P_1") (pintype "passive"))
    )
    (net (code "66") (name "unconnected-(PAD50-P-Pad1)") (class "Default")
      (node (ref "PAD50") (pin "1") (pinfunction "P_1") (pintype "passive"))
    )
    (net (code "67") (name "unconnected-(PAD51-P-Pad1)") (class "Default")
      (node (ref "PAD51") (pin "1") (pinfunction "P_1") (pintype "passive"))
    )
    (net (code "68") (name "unconnected-(PAD52-P-Pad1)") (class "Default")
      (node (ref "PAD52") (pin "1") (pinfunction "P_1") (pintype "passive"))
    )
    (net (code "69") (name "unconnected-(PAD53-P-Pad1)") (class "Default")
      (node (ref "PAD53") (pin "1") (pinfunction "P_1") (pintype "passive"))
    )
    (net (code "70") (name "unconnected-(PAD54-P-Pad1)") (class "Default")
      (node (ref "PAD54") (pin "1") (pinfunction "P_1") (pintype "passive"))
    )
    (net (code "71") (name "unconnected-(PAD55-P-Pad1)") (class "Default")
      (node (ref "PAD55") (pin "1") (pinfunction "P_1") (pintype "passive"))
    )
    (net (code "72") (name "unconnected-(PAD56-P-Pad1)") (class "Default")
      (node (ref "PAD56") (pin "1") (pinfunction "P_1") (pintype "passive"))
    )
    (net (code "73") (name "unconnected-(PAD57-P-Pad1)") (class "Default")
      (node (ref "PAD57") (pin "1") (pinfunction "P_1") (pintype "passive"))
    )
    (net (code "74") (name "unconnected-(PAD58-P-Pad1)") (class "Default")
      (node (ref "PAD58") (pin "1") (pinfunction "P_1") (pintype "passive"))
    )
    (net (code "75") (name "unconnected-(PAD59-P-Pad1)") (class "Default")
      (node (ref "PAD59") (pin "1") (pinfunction "P_1") (pintype "passive"))
    )
    (net (code "76") (name "unconnected-(PAD60-P-Pad1)") (class "Default")
      (node (ref "PAD60") (pin "1") (pinfunction "P_1") (pintype "passive"))
    )
    (net (code "77") (name "unconnected-(PAD61-P-Pad1)") (class "Default")
      (node (ref "PAD61") (pin "1") (pinfunction "P_1") (pintype "passive"))
    )
    (net (code "78") (name "unconnected-(PAD62-P-Pad1)") (class "Default")
      (node (ref "PAD62") (pin "1") (pinfunction "P_1") (pintype "passive"))
    )
    (net (code "79") (name "unconnected-(PAD63-P-Pad1)") (class "Default")
      (node (ref "PAD63") (pin "1") (pinfunction "P_1") (pintype "passive"))
    )
    (net (code "80") (name "unconnected-(PAD64-P-Pad1)") (class "Default")
      (node (ref "PAD64") (pin "1") (pinfunction "P_1") (pintype "passive"))
    )
    (net (code "81") (name "unconnected-(PAD65-P-Pad1)") (class "Default")
      (node (ref "PAD65") (pin "1") (pinfunction "P_1") (pintype "passive"))
    )
    (net (code "82") (name "unconnected-(PAD66-P-Pad1)") (class "Default")
      (node (ref "PAD66") (pin "1") (pinfunction "P_1") (pintype "passive"))
    )
    (net (code "83") (name "unconnected-(PAD67-P-Pad1)") (class "Default")
      (node (ref "PAD67") (pin "1") (pinfunction "P_1") (pintype "passive"))
    )
    (net (code "84") (name "unconnected-(PAD68-P-Pad1)") (class "Default")
      (node (ref "PAD68") (pin "1") (pinfunction "P_1") (pintype "passive"))
    )
    (net (code "85") (name "unconnected-(PAD69-P-Pad1)") (class "Default")
      (node (ref "PAD69") (pin "1") (pinfunction "P_1") (pintype "passive"))
    )
    (net (code "86") (name "unconnected-(PAD70-P-Pad1)") (class "Default")
      (node (ref "PAD70") (pin "1") (pinfunction "P_1") (pintype "passive"))
    )
    (net (code "87") (name "unconnected-(PAD71-P-Pad1)") (class "Default")
      (node (ref "PAD71") (pin "1") (pinfunction "P_1") (pintype "passive"))
    )
    (net (code "88") (name "unconnected-(PAD72-P-Pad1)") (class "Default")
      (node (ref "PAD72") (pin "1") (pinfunction "P_1") (pintype "passive"))
    )
    (net (code "89") (name "unconnected-(PAD73-P-Pad1)") (class "Default")
      (node (ref "PAD73") (pin "1") (pinfunction "P_1") (pintype "passive"))
    )
    (net (code "90") (name "unconnected-(PAD74-P-Pad1)") (class "Default")
      (node (ref "PAD74") (pin "1") (pinfunction "P_1") (pintype "passive"))
    )
    (net (code "91") (name "unconnected-(PAD75-P-Pad1)") (class "Default")
      (node (ref "PAD75") (pin "1") (pinfunction "P_1") (pintype "passive"))
    )
    (net (code "92") (name "unconnected-(PAD76-P-Pad1)") (class "Default")
      (node (ref "PAD76") (pin "1") (pinfunction "P_1") (pintype "passive"))
    )
    (net (code "93") (name "unconnected-(PAD77-P-Pad1)") (class "Default")
      (node (ref "PAD77") (pin "1") (pinfunction "P_1") (pintype "passive"))
    )
    (net (code "94") (name "unconnected-(PAD78-P-Pad1)") (class "Default")
      (node (ref "PAD78") (pin "1") (pinfunction "P_1") (pintype "passive"))
    )
    (net (code "95") (name "unconnected-(PAD79-P-Pad1)") (class "Default")
      (node (ref "PAD79") (pin "1") (pinfunction "P_1") (pintype "passive"))
    )
    (net (code "96") (name "unconnected-(PAD80-P-Pad1)") (class "Default")
      (node (ref "PAD80") (pin "1") (pinfunction "P_1") (pintype "passive"))
    )
    (net (code "97") (name "unconnected-(PAD81-P-Pad1)") (class "Default")
      (node (ref "PAD81") (pin "1") (pinfunction "P_1") (pintype "passive"))
    )
    (net (code "98") (name "unconnected-(PAD82-P-Pad1)") (class "Default")
      (node (ref "PAD82") (pin "1") (pinfunction "P_1") (pintype "passive"))
    )
    (net (code "99") (name "unconnected-(PAD83-P-Pad1)") (class "Default")
      (node (ref "PAD83") (pin "1") (pinfunction "P_1") (pintype "passive"))
    )
    (net (code "100") (name "unconnected-(PAD84-P-Pad1)") (class "Default")
      (node (ref "PAD84") (pin "1") (pinfunction "P_1") (pintype "passive"))
    )
    (net (code "101") (name "unconnected-(PAD85-P-Pad1)") (class "Default")
      (node (ref "PAD85") (pin "1") (pinfunction "P_1") (pintype "passive"))
    )
    (net (code "102") (name "unconnected-(PAD86-P-Pad1)") (class "Default")
      (node (ref "PAD86") (pin "1") (pinfunction "P_1") (pintype "passive"))
    )
    (net (code "103") (name "unconnected-(PAD87-P-Pad1)") (class "Default")
      (node (ref "PAD87") (pin "1") (pinfunction "P_1") (pintype "passive"))
    )
    (net (code "104") (name "unconnected-(PAD88-P-Pad1)") (class "Default")
      (node (ref "PAD88") (pin "1") (pinfunction "P_1") (pintype "passive"))
    )
    (net (code "105") (name "unconnected-(PAD89-P-Pad1)") (class "Default")
      (node (ref "PAD89") (pin "1") (pinfunction "P_1") (pintype "passive"))
    )
    (net (code "106") (name "unconnected-(PAD90-P-Pad1)") (class "Default")
      (node (ref "PAD90") (pin "1") (pinfunction "P_1") (pintype "passive"))
    )
    (net (code "107") (name "unconnected-(PAD91-P-Pad1)") (class "Default")
      (node (ref "PAD91") (pin "1") (pinfunction "P_1") (pintype "passive"))
    )
    (net (code "108") (name "unconnected-(PAD92-P-Pad1)") (class "Default")
      (node (ref "PAD92") (pin "1") (pinfunction "P_1") (pintype "passive"))
    )
    (net (code "109") (name "unconnected-(PAD93-P-Pad1)") (class "Default")
      (node (ref "PAD93") (pin "1") (pinfunction "P_1") (pintype "passive"))
    )
    (net (code "110") (name "unconnected-(PAD94-P-Pad1)") (class "Default")
      (node (ref "PAD94") (pin "1") (pinfunction "P_1") (pintype "passive"))
    )
    (net (code "111") (name "unconnected-(PAD95-P-Pad1)") (class "Default")
      (node (ref "PAD95") (pin "1") (pinfunction "P_1") (pintype "passive"))
    )
    (net (code "112") (name "unconnected-(PAD96-P-Pad1)") (class "Default")
      (node (ref "PAD96") (pin "1") (pinfunction "P_1") (pintype "passive"))
    )
  )
)
